# TPS6120x.net
KiCad netlist of a schematic drawn in Altium Designer
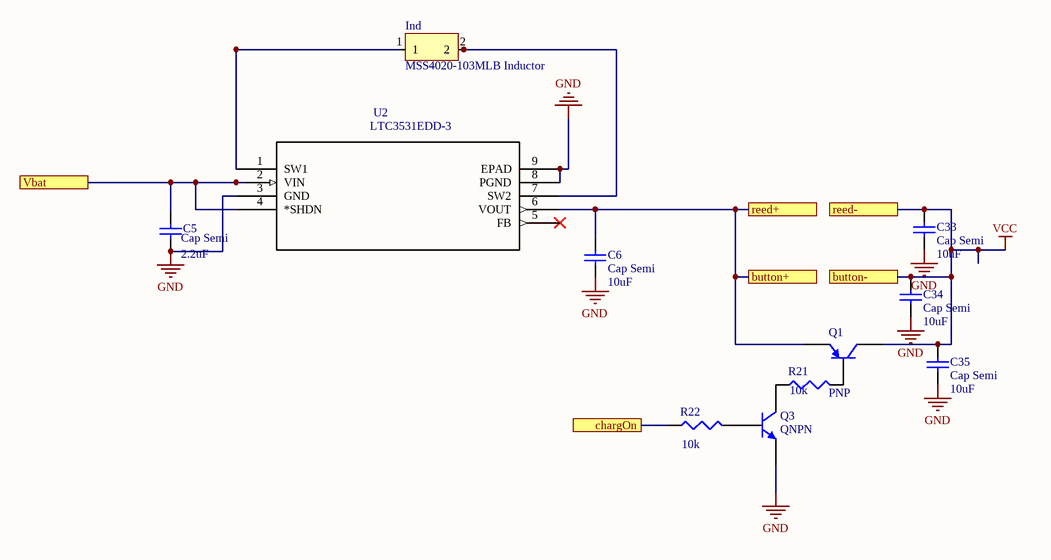
[diagram p0: TPS6120x.SchDoc]

(export (version "E")
  (design (tool "Eeschema 10.0.6"))
  (components
    (comp (ref "C5")
      (value "Cap Semi")
      (footprint "1608[0603]")
      (description "Capacitor (Semiconductor SIM Model)")
      (fields (field (name "ALTIUM_VALUE") "2.2uF") (field (name "PUBLISHER") "Altium Limited"))
      (libsource (lib "Miscellaneous Devices") (part "Cap Semi"))
    )
    (comp (ref "C6")
      (value "Cap Semi")
      (footprint "1608[0603]")
      (description "Capacitor (Semiconductor SIM Model)")
      (fields (field (name "ALTIUM_VALUE") "10uF") (field (name "PUBLISHER") "Altium Limited"))
      (libsource (lib "Miscellaneous Devices") (part "Cap Semi"))
    )
    (comp (ref "C33")
      (value "Cap Semi")
      (footprint "1608[0603]")
      (description "Capacitor (Semiconductor SIM Model)")
      (fields (field (name "ALTIUM_VALUE") "10uF") (field (name "PUBLISHER") "Altium Limited"))
      (libsource (lib "Miscellaneous Devices") (part "Cap Semi"))
    )
    (comp (ref "C34")
      (value "Cap Semi")
      (footprint "1608[0603]")
      (description "Capacitor (Semiconductor SIM Model)")
      (fields (field (name "ALTIUM_VALUE") "10uF") (field (name "PUBLISHER") "Altium Limited"))
      (libsource (lib "Miscellaneous Devices") (part "Cap Semi"))
    )
    (comp (ref "C35")
      (value "Cap Semi")
      (footprint "1608[0603]")
      (description "Capacitor (Semiconductor SIM Model)")
      (fields (field (name "ALTIUM_VALUE") "10uF") (field (name "PUBLISHER") "Altium Limited"))
      (libsource (lib "Miscellaneous Devices") (part "Cap Semi"))
    )
    (comp (ref "Ind")
      (value "MSS4020-103MLB Inductor")
      (footprint "MSS4020-103MLB")
      (libsource (lib "HGCDLibrary2") (part "MSS4020-103MLB Inductor"))
    )
    (comp (ref "Q1")
      (value "PNP")
      (footprint "SOT-23B_N")
      (description "PNP Bipolar Transistor")
      (fields (field (name "PUBLISHER") "Altium Limited"))
      (libsource (lib "Miscellaneous Devices") (part "PNP"))
    )
    (comp (ref "Q3")
      (value "QNPN")
      (footprint "SOT-23B_N")
      (description "NPN Bipolar Transistor")
      (fields (field (name "PUBLISHER") "Altium Limited"))
      (libsource (lib "Miscellaneous Devices") (part "QNPN"))
    )
    (comp (ref "R21")
      (value "10k")
      (footprint "J1-0603")
      (description "Resistor")
      (fields (field (name "Comment") "Res3") (field (name "PUBLISHER") "Altium Limited"))
      (libsource (lib "Miscellaneous Devices") (part "Res3"))
    )
    (comp (ref "R22")
      (value "10k")
      (footprint "J1-0603")
      (description "Resistor")
      (fields (field (name "Comment") "Res3") (field (name "PUBLISHER") "Altium Limited"))
      (libsource (lib "Miscellaneous Devices") (part "Res3"))
    )
    (comp (ref "U2")
      (value "LTC3531EDD-3")
      (footprint "LTC3531EDD-3")
      (description "LTC3531 - 200mA Buck-Boost Synchronous DC/DC Converters")
      (fields (field (name "MF") "Linear Technology"))
      (libsource (lib "HGCDLib") (part "LTC3531EDD-3"))
    )
  )
  (nets
    (net (code "1") (name "/Vbat") (class "Default")
      (node (ref "C5") (pin "2") (pinfunction "2_2") (pintype "passive"))
      (node (ref "U2") (pin "2") (pinfunction "VIN_2") (pintype "input"))
      (node (ref "U2") (pin "4") (pinfunction "*SHDN_4") (pintype "passive"))
    )
    (net (code "2") (name "/button+") (class "Default")
      (node (ref "C6") (pin "2") (pinfunction "2_2") (pintype "passive"))
      (node (ref "Q1") (pin "3") (pinfunction "E_3") (pintype "passive"))
      (node (ref "U2") (pin "6") (pinfunction "VOUT_6") (pintype "output"))
    )
    (net (code "3") (name "/chargOn") (class "Default")
      (node (ref "R22") (pin "1") (pinfunction "1_1") (pintype "passive"))
    )
    (net (code "4") (name "GND") (class "Default")
      (node (ref "C33") (pin "1") (pinfunction "1_1") (pintype "passive"))
      (node (ref "C34") (pin "1") (pinfunction "1_1") (pintype "passive"))
      (node (ref "C35") (pin "1") (pinfunction "1_1") (pintype "passive"))
      (node (ref "C5") (pin "1") (pinfunction "1_1") (pintype "passive"))
      (node (ref "C6") (pin "1") (pinfunction "1_1") (pintype "passive"))
      (node (ref "Q3") (pin "3") (pinfunction "E_3") (pintype "passive"))
      (node (ref "U2") (pin "3") (pinfunction "GND_3") (pintype "power_in"))
      (node (ref "U2") (pin "8") (pinfunction "PGND_8") (pintype "power_in"))
      (node (ref "U2") (pin "9") (pinfunction "EPAD_9") (pintype "passive"))
    )
    (net (code "5") (name "Net-(Q1-B)") (class "Default")
      (node (ref "Q1") (pin "2") (pinfunction "B_2") (pintype "passive"))
      (node (ref "R21") (pin "2") (pinfunction "2_2") (pintype "passive"))
    )
    (net (code "6") (name "Net-(Q3-B)") (class "Default")
      (node (ref "Q3") (pin "2") (pinfunction "B_2") (pintype "passive"))
      (node (ref "R22") (pin "2") (pinfunction "2_2") (pintype "passive"))
    )
    (net (code "7") (name "Net-(Q3-C)") (class "Default")
      (node (ref "Q3") (pin "1") (pinfunction "C_1") (pintype "passive"))
      (node (ref "R21") (pin "1") (pinfunction "1_1") (pintype "passive"))
    )
    (net (code "8") (name "Net-(U2-SW1)") (class "Default")
      (node (ref "Ind") (pin "1") (pinfunction "1_1") (pintype "passive"))
      (node (ref "U2") (pin "1") (pinfunction "SW1_1") (pintype "passive"))
    )
    (net (code "9") (name "Net-(U2-SW2)") (class "Default")
      (node (ref "Ind") (pin "2") (pinfunction "2_2") (pintype "passive"))
      (node (ref "U2") (pin "7") (pinfunction "SW2_7") (pintype "passive"))
    )
    (net (code "10") (name "VCC") (class "Default")
      (node (ref "C33") (pin "2") (pinfunction "2_2") (pintype "passive"))
      (node (ref "C34") (pin "2") (pinfunction "2_2") (pintype "passive"))
      (node (ref "C35") (pin "2") (pinfunction "2_2") (pintype "passive"))
      (node (ref "Q1") (pin "1") (pinfunction "C_1") (pintype "passive"))
    )
    (net (code "11") (name "unconnected-(U2-FB-Pad5)") (class "Default")
      (node (ref "U2") (pin "5") (pinfunction "FB_5") (pintype "output+no_connect"))
    )
  )
)
